# sparrow_ble_mic.net
KiCad netlist of a schematic drawn in EAGLE
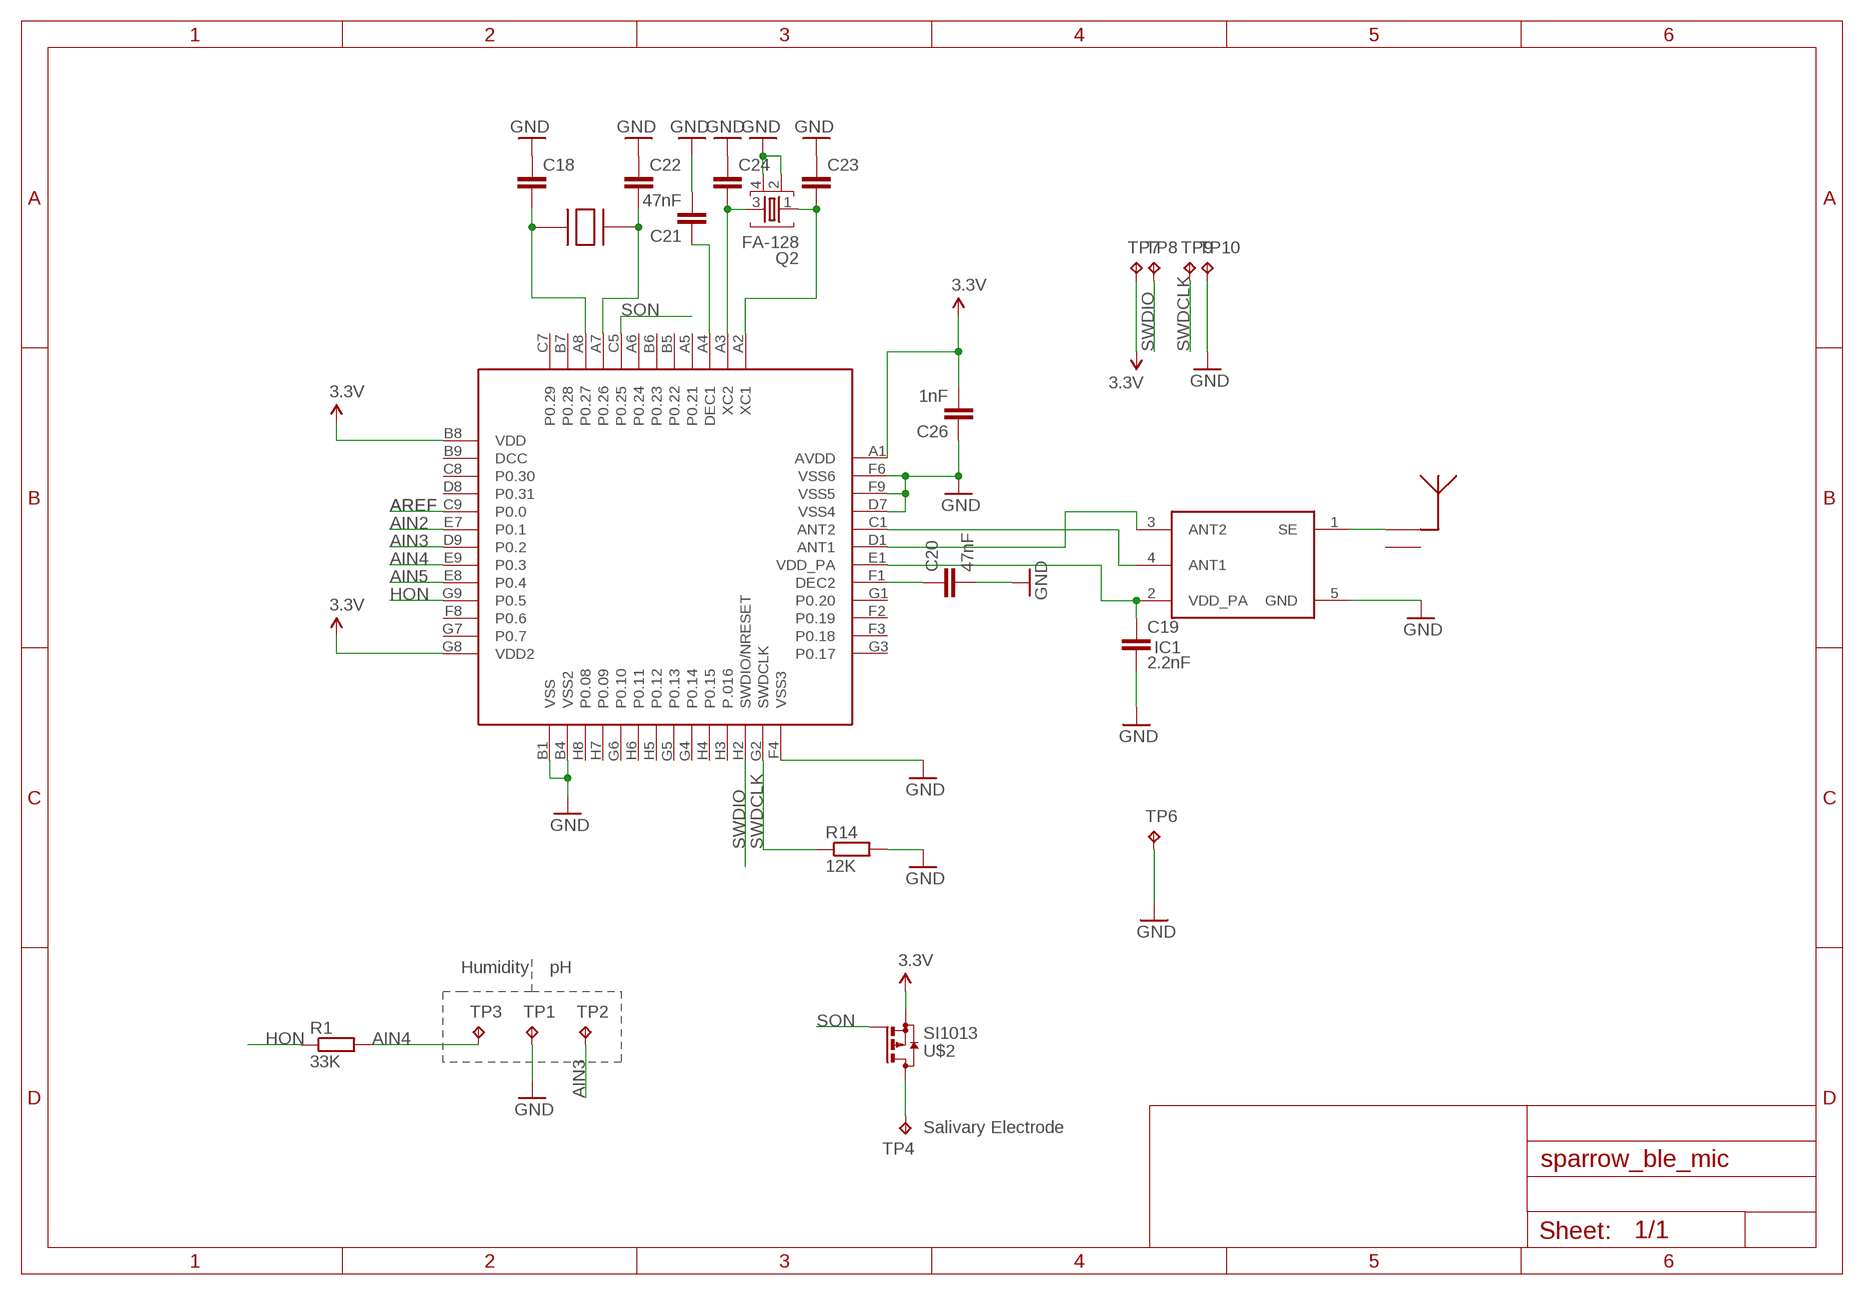
[diagram p0: schematic, sheet 1]

(export (version "E")
  (design (tool "Eeschema 10.0.6"))
  (components
    (comp (ref "C18")
      (value "C-EUC0201")
      (footprint "eagle-import:C0201")
      (libsource (lib "eagle-import") (part "C-EUC0201"))
    )
    (comp (ref "C19")
      (value "2.2nF")
      (footprint "eagle-import:C0201")
      (libsource (lib "eagle-import") (part "C-EUC0201"))
    )
    (comp (ref "C20")
      (value "47nF")
      (footprint "eagle-import:C0201")
      (libsource (lib "eagle-import") (part "C-EUC0201"))
    )
    (comp (ref "C21")
      (value "47nF")
      (footprint "eagle-import:C0201")
      (libsource (lib "eagle-import") (part "C-EUC0201"))
    )
    (comp (ref "C22")
      (value "C-EUC0201")
      (footprint "eagle-import:C0201")
      (libsource (lib "eagle-import") (part "C-EUC0201"))
    )
    (comp (ref "C23")
      (value "C-EUC0201")
      (footprint "eagle-import:C0201")
      (libsource (lib "eagle-import") (part "C-EUC0201"))
    )
    (comp (ref "C24")
      (value "C-EUC0201")
      (footprint "eagle-import:C0201")
      (libsource (lib "eagle-import") (part "C-EUC0201"))
    )
    (comp (ref "C26")
      (value "1nF")
      (footprint "eagle-import:C0201")
      (libsource (lib "eagle-import") (part "C-EUC0201"))
    )
    (comp (ref "IC1")
      (value "2450BM08B0003T")
      (footprint "eagle-import:2450BM08B0003T")
      (libsource (lib "eagle-import") (part "2450BM08B0003T"))
    )
    (comp (ref "IC3")
      (value "NRF51822_WLCSP")
      (footprint "eagle-import:WLCSP-CDAB62")
      (libsource (lib "eagle-import") (part "NRF51822_WLCSP"))
    )
    (comp (ref "Q2")
      (value "FA-128")
      (footprint "eagle-import:FA-128")
      (libsource (lib "eagle-import") (part "FA-128"))
    )
    (comp (ref "R1")
      (value "33K")
      (footprint "eagle-import:R0201")
      (libsource (lib "eagle-import") (part "R-EU_R0201"))
    )
    (comp (ref "R14")
      (value "12K")
      (footprint "eagle-import:R0201")
      (libsource (lib "eagle-import") (part "R-EU_R0201"))
    )
    (comp (ref "TP1")
      (value "TPTP10R")
      (footprint "eagle-import:TP10R")
      (libsource (lib "eagle-import") (part "TPTP10R"))
    )
    (comp (ref "TP2")
      (value "TPTP10R")
      (footprint "eagle-import:TP10R")
      (libsource (lib "eagle-import") (part "TPTP10R"))
    )
    (comp (ref "TP3")
      (value "TPTP10R")
      (footprint "eagle-import:TP10R")
      (libsource (lib "eagle-import") (part "TPTP10R"))
    )
    (comp (ref "TP4")
      (value "TPTP10R")
      (footprint "eagle-import:TP10R")
      (libsource (lib "eagle-import") (part "TPTP10R"))
    )
    (comp (ref "TP6")
      (value "TPTP20R")
      (footprint "eagle-import:TP20R")
      (libsource (lib "eagle-import") (part "TPTP20R"))
    )
    (comp (ref "TP7")
      (value "TPTP15R")
      (footprint "eagle-import:TP15R")
      (libsource (lib "eagle-import") (part "TPTP15R"))
    )
    (comp (ref "TP8")
      (value "TPTP15R")
      (footprint "eagle-import:TP15R")
      (libsource (lib "eagle-import") (part "TPTP15R"))
    )
    (comp (ref "TP9")
      (value "TPTP15R")
      (footprint "eagle-import:TP15R")
      (libsource (lib "eagle-import") (part "TPTP15R"))
    )
    (comp (ref "TP10")
      (value "TPTP15R")
      (footprint "eagle-import:TP15R")
      (libsource (lib "eagle-import") (part "TPTP15R"))
    )
    (comp (ref "U$1")
      (value "2450AT18A100")
      (footprint "eagle-import:2450AT18A100")
      (libsource (lib "eagle-import") (part "2450AT18A100"))
    )
    (comp (ref "U$2")
      (value "SI1013")
      (footprint "eagle-import:SC75_INFINEON")
      (libsource (lib "eagle-import") (part "SI1013"))
    )
    (comp (ref "U$4")
      (value "ABS05")
      (footprint "eagle-import:ABS05")
      (libsource (lib "eagle-import") (part "ABS05"))
    )
  )
  (nets
    (net (code "1") (name "/AIN2") (class "Default")
      (node (ref "IC3") (pin "E7") (pinfunction "P0.1_E7") (pintype "bidirectional"))
    )
    (net (code "2") (name "/AIN3") (class "Default")
      (node (ref "IC3") (pin "D9") (pinfunction "P0.2_D9") (pintype "bidirectional"))
      (node (ref "TP2") (pin "TP") (pinfunction "TP_TP") (pintype "input"))
    )
    (net (code "3") (name "/AIN4") (class "Default")
      (node (ref "IC3") (pin "E9") (pinfunction "P0.3_E9") (pintype "bidirectional"))
      (node (ref "R1") (pin "2") (pinfunction "2_2") (pintype "passive"))
      (node (ref "TP3") (pin "TP") (pinfunction "TP_TP") (pintype "input"))
    )
    (net (code "4") (name "/AIN5") (class "Default")
      (node (ref "IC3") (pin "E8") (pinfunction "P0.4_E8") (pintype "bidirectional"))
    )
    (net (code "5") (name "/AREF") (class "Default")
      (node (ref "IC3") (pin "C9") (pinfunction "P0.0_C9") (pintype "bidirectional"))
    )
    (net (code "6") (name "/HON") (class "Default")
      (node (ref "IC3") (pin "G9") (pinfunction "P0.5_G9") (pintype "bidirectional"))
      (node (ref "R1") (pin "1") (pinfunction "1_1") (pintype "passive"))
    )
    (net (code "7") (name "/SON") (class "Default")
      (node (ref "IC3") (pin "C5") (pinfunction "P0.25_C5") (pintype "bidirectional"))
      (node (ref "U$2") (pin "1") (pinfunction "G_1") (pintype "passive"))
    )
    (net (code "8") (name "/SWDCLK") (class "Default")
      (node (ref "IC3") (pin "G2") (pinfunction "SWDCLK_G2") (pintype "bidirectional"))
      (node (ref "R14") (pin "1") (pinfunction "1_1") (pintype "passive"))
      (node (ref "TP9") (pin "TP") (pinfunction "TP_TP") (pintype "input"))
    )
    (net (code "9") (name "/SWDIO") (class "Default")
      (node (ref "IC3") (pin "H2") (pinfunction "SWDIO/NRESET_H2") (pintype "bidirectional"))
      (node (ref "TP8") (pin "TP") (pinfunction "TP_TP") (pintype "input"))
    )
    (net (code "10") (name "3.3V") (class "Default")
      (node (ref "C26") (pin "2") (pinfunction "2_2") (pintype "passive"))
      (node (ref "IC3") (pin "A1") (pinfunction "AVDD_A1") (pintype "bidirectional"))
      (node (ref "IC3") (pin "B8") (pinfunction "VDD_B8") (pintype "bidirectional"))
      (node (ref "IC3") (pin "G8") (pinfunction "VDD2_G8") (pintype "bidirectional"))
      (node (ref "TP7") (pin "TP") (pinfunction "TP_TP") (pintype "input"))
      (node (ref "U$2") (pin "2") (pinfunction "S_2") (pintype "passive"))
    )
    (net (code "11") (name "GND") (class "Default")
      (node (ref "C18") (pin "1") (pinfunction "1_1") (pintype "passive"))
      (node (ref "C19") (pin "2") (pinfunction "2_2") (pintype "passive"))
      (node (ref "C20") (pin "2") (pinfunction "2_2") (pintype "passive"))
      (node (ref "C21") (pin "2") (pinfunction "2_2") (pintype "passive"))
      (node (ref "C22") (pin "1") (pinfunction "1_1") (pintype "passive"))
      (node (ref "C23") (pin "1") (pinfunction "1_1") (pintype "passive"))
      (node (ref "C24") (pin "1") (pinfunction "1_1") (pintype "passive"))
      (node (ref "C26") (pin "1") (pinfunction "1_1") (pintype "passive"))
      (node (ref "IC1") (pin "5") (pinfunction "GND_5") (pintype "bidirectional"))
      (node (ref "IC3") (pin "B1") (pinfunction "VSS_B1") (pintype "bidirectional"))
      (node (ref "IC3") (pin "B4") (pinfunction "VSS2_B4") (pintype "bidirectional"))
      (node (ref "IC3") (pin "D7") (pinfunction "VSS4_D7") (pintype "bidirectional"))
      (node (ref "IC3") (pin "F4") (pinfunction "VSS3_F4") (pintype "bidirectional"))
      (node (ref "IC3") (pin "F6") (pinfunction "VSS6_F6") (pintype "bidirectional"))
      (node (ref "IC3") (pin "F9") (pinfunction "VSS5_F9") (pintype "bidirectional"))
      (node (ref "Q2") (pin "2") (pinfunction "2_2") (pintype "passive"))
      (node (ref "Q2") (pin "4") (pinfunction "4_4") (pintype "passive"))
      (node (ref "R14") (pin "2") (pinfunction "2_2") (pintype "passive"))
      (node (ref "TP1") (pin "TP") (pinfunction "TP_TP") (pintype "input"))
      (node (ref "TP10") (pin "TP") (pinfunction "TP_TP") (pintype "input"))
      (node (ref "TP6") (pin "TP") (pinfunction "TP_TP") (pintype "input"))
    )
    (net (code "12") (name "Net-(IC1-ANT1)") (class "Default")
      (node (ref "IC1") (pin "4") (pinfunction "ANT1_4") (pintype "bidirectional"))
      (node (ref "IC3") (pin "C1") (pinfunction "ANT2_C1") (pintype "bidirectional"))
    )
    (net (code "13") (name "Net-(IC1-ANT2)") (class "Default")
      (node (ref "IC1") (pin "3") (pinfunction "ANT2_3") (pintype "bidirectional"))
      (node (ref "IC3") (pin "D1") (pinfunction "ANT1_D1") (pintype "bidirectional"))
    )
    (net (code "14") (name "Net-(IC1-SE)") (class "Default")
      (node (ref "IC1") (pin "1") (pinfunction "SE_1") (pintype "bidirectional"))
      (node (ref "U$1") (pin "P$1") (pinfunction "P$1_P$1") (pintype "bidirectional"))
    )
    (net (code "15") (name "Net-(IC1-VDD_PA)") (class "Default")
      (node (ref "C19") (pin "1") (pinfunction "1_1") (pintype "passive"))
      (node (ref "IC1") (pin "2") (pinfunction "VDD_PA_2") (pintype "bidirectional"))
      (node (ref "IC3") (pin "E1") (pinfunction "VDD_PA_E1") (pintype "bidirectional"))
    )
    (net (code "16") (name "Net-(IC3-DEC1)") (class "Default")
      (node (ref "C21") (pin "1") (pinfunction "1_1") (pintype "passive"))
      (node (ref "IC3") (pin "A4") (pinfunction "DEC1_A4") (pintype "bidirectional"))
    )
    (net (code "17") (name "Net-(IC3-DEC2)") (class "Default")
      (node (ref "C20") (pin "1") (pinfunction "1_1") (pintype "passive"))
      (node (ref "IC3") (pin "F1") (pinfunction "DEC2_F1") (pintype "bidirectional"))
    )
    (net (code "18") (name "Net-(IC3-P0.26)") (class "Default")
      (node (ref "C22") (pin "2") (pinfunction "2_2") (pintype "passive"))
      (node (ref "IC3") (pin "A7") (pinfunction "P0.26_A7") (pintype "bidirectional"))
      (node (ref "U$4") (pin "P$2") (pinfunction "P$2_P$2") (pintype "bidirectional"))
    )
    (net (code "19") (name "Net-(IC3-P0.27)") (class "Default")
      (node (ref "C18") (pin "2") (pinfunction "2_2") (pintype "passive"))
      (node (ref "IC3") (pin "A8") (pinfunction "P0.27_A8") (pintype "bidirectional"))
      (node (ref "U$4") (pin "P$1") (pinfunction "P$1_P$1") (pintype "bidirectional"))
    )
    (net (code "20") (name "Net-(IC3-XC1)") (class "Default")
      (node (ref "C23") (pin "2") (pinfunction "2_2") (pintype "passive"))
      (node (ref "IC3") (pin "A2") (pinfunction "XC1_A2") (pintype "bidirectional"))
      (node (ref "Q2") (pin "1") (pinfunction "1_1") (pintype "passive"))
    )
    (net (code "21") (name "Net-(IC3-XC2)") (class "Default")
      (node (ref "C24") (pin "2") (pinfunction "2_2") (pintype "passive"))
      (node (ref "IC3") (pin "A3") (pinfunction "XC2_A3") (pintype "bidirectional"))
      (node (ref "Q2") (pin "3") (pinfunction "3_3") (pintype "passive"))
    )
    (net (code "22") (name "Net-(U$2-D)") (class "Default")
      (node (ref "TP4") (pin "TP") (pinfunction "TP_TP") (pintype "input"))
      (node (ref "U$2") (pin "3") (pinfunction "D_3") (pintype "passive"))
    )
    (net (code "23") (name "unconnected-(IC3-DCC-PadB9)") (class "Default")
      (node (ref "IC3") (pin "B9") (pinfunction "DCC_B9") (pintype "bidirectional"))
    )
    (net (code "24") (name "unconnected-(IC3-P.016-PadH3)") (class "Default")
      (node (ref "IC3") (pin "H3") (pinfunction "P.016_H3") (pintype "bidirectional"))
    )
    (net (code "25") (name "unconnected-(IC3-P0.6-PadF8)") (class "Default")
      (node (ref "IC3") (pin "F8") (pinfunction "P0.6_F8") (pintype "bidirectional"))
    )
    (net (code "26") (name "unconnected-(IC3-P0.7-PadG7)") (class "Default")
      (node (ref "IC3") (pin "G7") (pinfunction "P0.7_G7") (pintype "bidirectional"))
    )
    (net (code "27") (name "unconnected-(IC3-P0.08-PadH8)") (class "Default")
      (node (ref "IC3") (pin "H8") (pinfunction "P0.08_H8") (pintype "bidirectional"))
    )
    (net (code "28") (name "unconnected-(IC3-P0.09-PadH7)") (class "Default")
      (node (ref "IC3") (pin "H7") (pinfunction "P0.09_H7") (pintype "bidirectional"))
    )
    (net (code "29") (name "unconnected-(IC3-P0.10-PadG6)") (class "Default")
      (node (ref "IC3") (pin "G6") (pinfunction "P0.10_G6") (pintype "bidirectional"))
    )
    (net (code "30") (name "unconnected-(IC3-P0.11-PadH6)") (class "Default")
      (node (ref "IC3") (pin "H6") (pinfunction "P0.11_H6") (pintype "bidirectional"))
    )
    (net (code "31") (name "unconnected-(IC3-P0.12-PadH5)") (class "Default")
      (node (ref "IC3") (pin "H5") (pinfunction "P0.12_H5") (pintype "bidirectional"))
    )
    (net (code "32") (name "unconnected-(IC3-P0.13-PadG5)") (class "Default")
      (node (ref "IC3") (pin "G5") (pinfunction "P0.13_G5") (pintype "bidirectional"))
    )
    (net (code "33") (name "unconnected-(IC3-P0.14-PadG4)") (class "Default")
      (node (ref "IC3") (pin "G4") (pinfunction "P0.14_G4") (pintype "bidirectional"))
    )
    (net (code "34") (name "unconnected-(IC3-P0.15-PadH4)") (class "Default")
      (node (ref "IC3") (pin "H4") (pinfunction "P0.15_H4") (pintype "bidirectional"))
    )
    (net (code "35") (name "unconnected-(IC3-P0.17-PadG3)") (class "Default")
      (node (ref "IC3") (pin "G3") (pinfunction "P0.17_G3") (pintype "bidirectional"))
    )
    (net (code "36") (name "unconnected-(IC3-P0.18-PadF3)") (class "Default")
      (node (ref "IC3") (pin "F3") (pinfunction "P0.18_F3") (pintype "bidirectional"))
    )
    (net (code "37") (name "unconnected-(IC3-P0.19-PadF2)") (class "Default")
      (node (ref "IC3") (pin "F2") (pinfunction "P0.19_F2") (pintype "bidirectional"))
    )
    (net (code "38") (name "unconnected-(IC3-P0.20-PadG1)") (class "Default")
      (node (ref "IC3") (pin "G1") (pinfunction "P0.20_G1") (pintype "bidirectional"))
    )
    (net (code "39") (name "unconnected-(IC3-P0.21-PadA5)") (class "Default")
      (node (ref "IC3") (pin "A5") (pinfunction "P0.21_A5") (pintype "bidirectional"))
    )
    (net (code "40") (name "unconnected-(IC3-P0.22-PadB5)") (class "Default")
      (node (ref "IC3") (pin "B5") (pinfunction "P0.22_B5") (pintype "bidirectional"))
    )
    (net (code "41") (name "unconnected-(IC3-P0.23-PadB6)") (class "Default")
      (node (ref "IC3") (pin "B6") (pinfunction "P0.23_B6") (pintype "bidirectional"))
    )
    (net (code "42") (name "unconnected-(IC3-P0.24-PadA6)") (class "Default")
      (node (ref "IC3") (pin "A6") (pinfunction "P0.24_A6") (pintype "bidirectional"))
    )
    (net (code "43") (name "unconnected-(IC3-P0.28-PadB7)") (class "Default")
      (node (ref "IC3") (pin "B7") (pinfunction "P0.28_B7") (pintype "bidirectional"))
    )
    (net (code "44") (name "unconnected-(IC3-P0.29-PadC7)") (class "Default")
      (node (ref "IC3") (pin "C7") (pinfunction "P0.29_C7") (pintype "bidirectional"))
    )
    (net (code "45") (name "unconnected-(IC3-P0.30-PadC8)") (class "Default")
      (node (ref "IC3") (pin "C8") (pinfunction "P0.30_C8") (pintype "bidirectional"))
    )
    (net (code "46") (name "unconnected-(IC3-P0.31-PadD8)") (class "Default")
      (node (ref "IC3") (pin "D8") (pinfunction "P0.31_D8") (pintype "bidirectional"))
    )
    (net (code "47") (name "unconnected-(U$1-PadP$2)") (class "Default")
      (node (ref "U$1") (pin "P$2") (pinfunction "P$2_P$2") (pintype "bidirectional"))
    )
  )
)
